# ross_comp.net
KiCad netlist of a schematic drawn in EAGLE
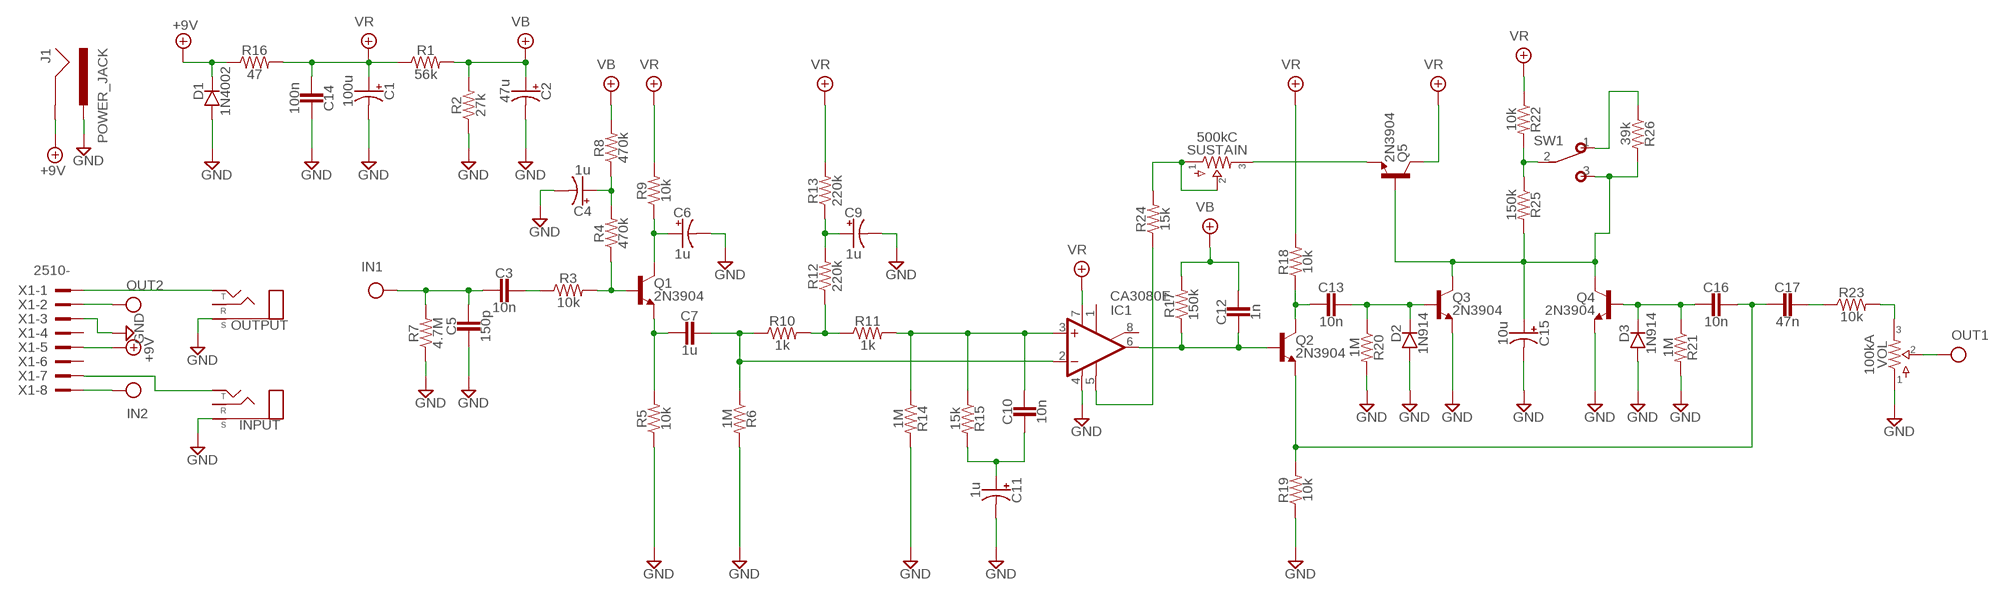
[diagram p0: schematic, sheet 1]

(export (version "E")
  (design (tool "Eeschema 10.0.6"))
  (components
    (comp (ref "C1")
      (value "100u")
      (footprint "eagle-import:040_020")
      (libsource (lib "eagle-import") (part "0400"))
    )
    (comp (ref "C2")
      (value "47u")
      (footprint "eagle-import:040_020")
      (libsource (lib "eagle-import") (part "0400"))
    )
    (comp (ref "C3")
      (value "10n")
      (footprint "eagle-import:BOX_SMALL")
      (libsource (lib "eagle-import") (part "CER/FILMBOX.1"))
    )
    (comp (ref "C4")
      (value "1u")
      (footprint "eagle-import:040_020")
      (libsource (lib "eagle-import") (part "0400"))
    )
    (comp (ref "C5")
      (value "150p")
      (footprint "eagle-import:050X030_025_2")
      (libsource (lib "eagle-import") (part "CER/FILM2"))
    )
    (comp (ref "C6")
      (value "1u")
      (footprint "eagle-import:040_020")
      (libsource (lib "eagle-import") (part "0400"))
    )
    (comp (ref "C7")
      (value "1u")
      (footprint "eagle-import:BOX_BIG")
      (libsource (lib "eagle-import") (part "CER/FILMBOX.3"))
    )
    (comp (ref "C9")
      (value "1u")
      (footprint "eagle-import:040_020")
      (libsource (lib "eagle-import") (part "0400"))
    )
    (comp (ref "C10")
      (value "10n")
      (footprint "eagle-import:BOX_SMALL")
      (libsource (lib "eagle-import") (part "CER/FILMBOX.1"))
    )
    (comp (ref "C11")
      (value "1u")
      (footprint "eagle-import:040_020")
      (libsource (lib "eagle-import") (part "0400"))
    )
    (comp (ref "C12")
      (value "1n")
      (footprint "eagle-import:BOX_SMALL")
      (libsource (lib "eagle-import") (part "CER/FILMBOX.1"))
    )
    (comp (ref "C13")
      (value "10n")
      (footprint "eagle-import:BOX_SMALL")
      (libsource (lib "eagle-import") (part "CER/FILMBOX.1"))
    )
    (comp (ref "C14")
      (value "100n")
      (footprint "eagle-import:BOX_SMALL")
      (libsource (lib "eagle-import") (part "CER/FILMBOX.1"))
    )
    (comp (ref "C15")
      (value "10u")
      (footprint "eagle-import:040_020")
      (libsource (lib "eagle-import") (part "0400"))
    )
    (comp (ref "C16")
      (value "10n")
      (footprint "eagle-import:BOX_SMALL")
      (libsource (lib "eagle-import") (part "CER/FILMBOX.1"))
    )
    (comp (ref "C17")
      (value "47n")
      (footprint "eagle-import:BOX_SMALL")
      (libsource (lib "eagle-import") (part "CER/FILMBOX.1"))
    )
    (comp (ref "D1")
      (value "1N4002")
      (footprint "eagle-import:DO41-2")
      (libsource (lib "eagle-import") (part "DO41.2"))
    )
    (comp (ref "D2")
      (value "1N914")
      (footprint "eagle-import:DO35-2")
      (libsource (lib "eagle-import") (part "DO35.2"))
    )
    (comp (ref "D3")
      (value "1N914")
      (footprint "eagle-import:DO35-2")
      (libsource (lib "eagle-import") (part "DO35.2"))
    )
    (comp (ref "IC1")
      (value "CA3080E")
      (footprint "eagle-import:DIL08")
      (libsource (lib "eagle-import") (part "3080TH"))
    )
    (comp (ref "INPUT")
      (value "STEREONMJ")
      (footprint "eagle-import:NMJ6HCD2")
      (libsource (lib "eagle-import") (part "STEREONMJ"))
    )
    (comp (ref "J1")
      (value "POWER_JACK")
      (footprint "eagle-import:POWER_JACK_PTH")
      (libsource (lib "eagle-import") (part "POWER_JACK"))
    )
    (comp (ref "OUTPUT")
      (value "STEREONMJ")
      (footprint "eagle-import:NMJ6HCD2")
      (libsource (lib "eagle-import") (part "STEREONMJ"))
    )
    (comp (ref "Q1")
      (value "2N3904")
      (footprint "eagle-import:TO92-")
      (libsource (lib "eagle-import") (part "2N3904"))
    )
    (comp (ref "Q2")
      (value "2N3904")
      (footprint "eagle-import:TO92-")
      (libsource (lib "eagle-import") (part "2N3904"))
    )
    (comp (ref "Q3")
      (value "2N3904")
      (footprint "eagle-import:TO92-")
      (libsource (lib "eagle-import") (part "2N3904"))
    )
    (comp (ref "Q4")
      (value "2N3904")
      (footprint "eagle-import:TO92-")
      (libsource (lib "eagle-import") (part "2N3904"))
    )
    (comp (ref "Q5")
      (value "2N3904")
      (footprint "eagle-import:TO92-")
      (libsource (lib "eagle-import") (part "2N3904"))
    )
    (comp (ref "R1")
      (value "56k")
      (footprint "eagle-import:R0207_3")
      (libsource (lib "eagle-import") (part "R_.3B"))
    )
    (comp (ref "R2")
      (value "27k")
      (footprint "eagle-import:R0207_3")
      (libsource (lib "eagle-import") (part "R_.3B"))
    )
    (comp (ref "R3")
      (value "10k")
      (footprint "eagle-import:R0207_3")
      (libsource (lib "eagle-import") (part "R_.3B"))
    )
    (comp (ref "R4")
      (value "470k")
      (footprint "eagle-import:R0207_3")
      (libsource (lib "eagle-import") (part "R_.3B"))
    )
    (comp (ref "R5")
      (value "10k")
      (footprint "eagle-import:R0207_3")
      (libsource (lib "eagle-import") (part "R_.3B"))
    )
    (comp (ref "R6")
      (value "1M")
      (footprint "eagle-import:R0207_3")
      (libsource (lib "eagle-import") (part "R_.3B"))
    )
    (comp (ref "R7")
      (value "4.7M")
      (footprint "eagle-import:R0207_3")
      (libsource (lib "eagle-import") (part "R_.3B"))
    )
    (comp (ref "R8")
      (value "470k")
      (footprint "eagle-import:R0207_3")
      (libsource (lib "eagle-import") (part "R_.3B"))
    )
    (comp (ref "R9")
      (value "10k")
      (footprint "eagle-import:R0207_3")
      (libsource (lib "eagle-import") (part "R_.3B"))
    )
    (comp (ref "R10")
      (value "1k")
      (footprint "eagle-import:R0207_3")
      (libsource (lib "eagle-import") (part "R_.3B"))
    )
    (comp (ref "R11")
      (value "1k")
      (footprint "eagle-import:R0207_3")
      (libsource (lib "eagle-import") (part "R_.3B"))
    )
    (comp (ref "R12")
      (value "220k")
      (footprint "eagle-import:R0207_3")
      (libsource (lib "eagle-import") (part "R_.3B"))
    )
    (comp (ref "R13")
      (value "220k")
      (footprint "eagle-import:R0207_3")
      (libsource (lib "eagle-import") (part "R_.3B"))
    )
    (comp (ref "R14")
      (value "1M")
      (footprint "eagle-import:R0207_3")
      (libsource (lib "eagle-import") (part "R_.3B"))
    )
    (comp (ref "R15")
      (value "15k")
      (footprint "eagle-import:R0207_3")
      (libsource (lib "eagle-import") (part "R_.3B"))
    )
    (comp (ref "R16")
      (value "47")
      (footprint "eagle-import:R0207_3")
      (libsource (lib "eagle-import") (part "R_.3B"))
    )
    (comp (ref "R17")
      (value "150k")
      (footprint "eagle-import:R0207_3")
      (libsource (lib "eagle-import") (part "R_.3B"))
    )
    (comp (ref "R18")
      (value "10k")
      (footprint "eagle-import:R0207_3")
      (libsource (lib "eagle-import") (part "R_.3B"))
    )
    (comp (ref "R19")
      (value "10k")
      (footprint "eagle-import:R0207_3")
      (libsource (lib "eagle-import") (part "R_.3B"))
    )
    (comp (ref "R20")
      (value "1M")
      (footprint "eagle-import:R0207_3")
      (libsource (lib "eagle-import") (part "R_.3B"))
    )
    (comp (ref "R21")
      (value "1M")
      (footprint "eagle-import:R0207_3")
      (libsource (lib "eagle-import") (part "R_.3B"))
    )
    (comp (ref "R22")
      (value "10k")
      (footprint "eagle-import:R0207_3")
      (libsource (lib "eagle-import") (part "R_.3B"))
    )
    (comp (ref "R23")
      (value "10k")
      (footprint "eagle-import:R0207_3")
      (libsource (lib "eagle-import") (part "R_.3B"))
    )
    (comp (ref "R24")
      (value "15k")
      (footprint "eagle-import:R0207_3")
      (libsource (lib "eagle-import") (part "R_.3B"))
    )
    (comp (ref "R25")
      (value "150k")
      (footprint "eagle-import:R0207_3")
      (libsource (lib "eagle-import") (part "R_.3B"))
    )
    (comp (ref "R26")
      (value "39k")
      (footprint "eagle-import:R0207_3")
      (libsource (lib "eagle-import") (part "R_.3B"))
    )
    (comp (ref "SUSTAIN")
      (value "500kC")
      (footprint "eagle-import:16MM")
      (libsource (lib "eagle-import") (part "POTS16MM"))
    )
    (comp (ref "SW1")
      (value "SPDT")
      (footprint "eagle-import:M9040P")
      (libsource (lib "eagle-import") (part "SPDT"))
    )
    (comp (ref "VOL")
      (value "100kA")
      (footprint "eagle-import:16MM")
      (libsource (lib "eagle-import") (part "POTS16MM"))
    )
    (comp (ref "X1")
      (value "2510-")
      (footprint "eagle-import:PAK100_2500-10")
      (fields (field (name "MF") "3M") (field (name "MPN") "2510-6002UB"))
      (libsource (lib "eagle-import") (part "2510-"))
    )
  )
  (nets
    (net (code "1") (name "+9V") (class "Default")
      (node (ref "D1") (pin "C") (pinfunction "C_C") (pintype "passive"))
      (node (ref "J1") (pin "GND") (pinfunction "GND_GND") (pintype "bidirectional"))
      (node (ref "R16") (pin "1") (pinfunction "1_1") (pintype "passive"))
      (node (ref "X1") (pin "5") (pinfunction "KL_5") (pintype "passive"))
    )
    (net (code "2") (name "GND") (class "Default")
      (node (ref "C1") (pin "-") (pinfunction "-_-") (pintype "passive"))
      (node (ref "C11") (pin "-") (pinfunction "-_-") (pintype "passive"))
      (node (ref "C14") (pin "1") (pinfunction "1_1") (pintype "passive"))
      (node (ref "C15") (pin "-") (pinfunction "-_-") (pintype "passive"))
      (node (ref "C2") (pin "-") (pinfunction "-_-") (pintype "passive"))
      (node (ref "C4") (pin "-") (pinfunction "-_-") (pintype "passive"))
      (node (ref "C5") (pin "2") (pinfunction "2_2") (pintype "passive"))
      (node (ref "C6") (pin "-") (pinfunction "-_-") (pintype "passive"))
      (node (ref "C9") (pin "-") (pinfunction "-_-") (pintype "passive"))
      (node (ref "D1") (pin "A") (pinfunction "A_A") (pintype "passive"))
      (node (ref "D2") (pin "A") (pinfunction "A_A") (pintype "passive"))
      (node (ref "D3") (pin "A") (pinfunction "A_A") (pintype "passive"))
      (node (ref "IC1") (pin "4") (pinfunction "V-_4") (pintype "power_in"))
      (node (ref "INPUT") (pin "S") (pinfunction "S_S") (pintype "passive"))
      (node (ref "J1") (pin "PWR") (pinfunction "PWR_PWR") (pintype "bidirectional"))
      (node (ref "OUTPUT") (pin "S") (pinfunction "S_S") (pintype "passive"))
      (node (ref "Q3") (pin "3") (pinfunction "E_3") (pintype "passive"))
      (node (ref "Q4") (pin "3") (pinfunction "E_3") (pintype "passive"))
      (node (ref "R14") (pin "2") (pinfunction "2_2") (pintype "passive"))
      (node (ref "R19") (pin "1") (pinfunction "1_1") (pintype "passive"))
      (node (ref "R2") (pin "1") (pinfunction "1_1") (pintype "passive"))
      (node (ref "R20") (pin "2") (pinfunction "2_2") (pintype "passive"))
      (node (ref "R21") (pin "2") (pinfunction "2_2") (pintype "passive"))
      (node (ref "R5") (pin "1") (pinfunction "1_1") (pintype "passive"))
      (node (ref "R6") (pin "2") (pinfunction "2_2") (pintype "passive"))
      (node (ref "R7") (pin "1") (pinfunction "1_1") (pintype "passive"))
      (node (ref "VOL") (pin "1") (pinfunction "1_1") (pintype "passive"))
      (node (ref "X1") (pin "3") (pinfunction "KL_3") (pintype "passive"))
    )
    (net (code "3") (name "IN") (class "Default")
      (node (ref "C3") (pin "2") (pinfunction "2_2") (pintype "passive"))
      (node (ref "C5") (pin "1") (pinfunction "1_1") (pintype "passive"))
      (node (ref "R7") (pin "2") (pinfunction "2_2") (pintype "passive"))
      (node (ref "X1") (pin "8") (pinfunction "KL_8") (pintype "passive"))
    )
    (net (code "4") (name "Net-(C3-Pad1)") (class "Default")
      (node (ref "C3") (pin "1") (pinfunction "1_1") (pintype "passive"))
      (node (ref "R3") (pin "1") (pinfunction "1_1") (pintype "passive"))
    )
    (net (code "5") (name "Net-(C4-Pad+)") (class "Default")
      (node (ref "C4") (pin "+") (pinfunction "+_+") (pintype "passive"))
      (node (ref "R4") (pin "2") (pinfunction "2_2") (pintype "passive"))
      (node (ref "R8") (pin "1") (pinfunction "1_1") (pintype "passive"))
    )
    (net (code "6") (name "Net-(C9-Pad+)") (class "Default")
      (node (ref "C9") (pin "+") (pinfunction "+_+") (pintype "passive"))
      (node (ref "R12") (pin "2") (pinfunction "2_2") (pintype "passive"))
      (node (ref "R13") (pin "1") (pinfunction "1_1") (pintype "passive"))
    )
    (net (code "7") (name "Net-(C10-Pad2)") (class "Default")
      (node (ref "C10") (pin "2") (pinfunction "2_2") (pintype "passive"))
      (node (ref "C11") (pin "+") (pinfunction "+_+") (pintype "passive"))
      (node (ref "R15") (pin "2") (pinfunction "2_2") (pintype "passive"))
    )
    (net (code "8") (name "Net-(C17-Pad1)") (class "Default")
      (node (ref "C17") (pin "1") (pinfunction "1_1") (pintype "passive"))
      (node (ref "R23") (pin "1") (pinfunction "1_1") (pintype "passive"))
    )
    (net (code "9") (name "Net-(IC1-+IN)") (class "Default")
      (node (ref "C10") (pin "1") (pinfunction "1_1") (pintype "passive"))
      (node (ref "IC1") (pin "3") (pinfunction "+IN_3") (pintype "input"))
      (node (ref "R11") (pin "2") (pinfunction "2_2") (pintype "passive"))
      (node (ref "R14") (pin "1") (pinfunction "1_1") (pintype "passive"))
      (node (ref "R15") (pin "1") (pinfunction "1_1") (pintype "passive"))
    )
    (net (code "10") (name "Net-(IC1--IN)") (class "Default")
      (node (ref "C7") (pin "1") (pinfunction "1_1") (pintype "passive"))
      (node (ref "IC1") (pin "2") (pinfunction "-IN_2") (pintype "input"))
      (node (ref "R10") (pin "1") (pinfunction "1_1") (pintype "passive"))
      (node (ref "R6") (pin "1") (pinfunction "1_1") (pintype "passive"))
    )
    (net (code "11") (name "Net-(IC1-OPT)") (class "Default")
      (node (ref "IC1") (pin "5") (pinfunction "OPT_5") (pintype "passive"))
      (node (ref "R24") (pin "1") (pinfunction "1_1") (pintype "passive"))
    )
    (net (code "12") (name "Net-(IC1-OUT)") (class "Default")
      (node (ref "C12") (pin "2") (pinfunction "2_2") (pintype "passive"))
      (node (ref "IC1") (pin "6") (pinfunction "OUT_6") (pintype "output"))
      (node (ref "Q2") (pin "2") (pinfunction "B_2") (pintype "passive"))
      (node (ref "R17") (pin "1") (pinfunction "1_1") (pintype "passive"))
    )
    (net (code "13") (name "Net-(Q1-B)") (class "Default")
      (node (ref "Q1") (pin "2") (pinfunction "B_2") (pintype "passive"))
      (node (ref "R3") (pin "2") (pinfunction "2_2") (pintype "passive"))
      (node (ref "R4") (pin "1") (pinfunction "1_1") (pintype "passive"))
    )
    (net (code "14") (name "Net-(Q1-C)") (class "Default")
      (node (ref "C6") (pin "+") (pinfunction "+_+") (pintype "passive"))
      (node (ref "Q1") (pin "1") (pinfunction "C_1") (pintype "passive"))
      (node (ref "R9") (pin "1") (pinfunction "1_1") (pintype "passive"))
    )
    (net (code "15") (name "Net-(Q1-E)") (class "Default")
      (node (ref "C7") (pin "2") (pinfunction "2_2") (pintype "passive"))
      (node (ref "Q1") (pin "3") (pinfunction "E_3") (pintype "passive"))
      (node (ref "R5") (pin "2") (pinfunction "2_2") (pintype "passive"))
    )
    (net (code "16") (name "Net-(Q2-C)") (class "Default")
      (node (ref "C13") (pin "2") (pinfunction "2_2") (pintype "passive"))
      (node (ref "Q2") (pin "1") (pinfunction "C_1") (pintype "passive"))
      (node (ref "R18") (pin "1") (pinfunction "1_1") (pintype "passive"))
    )
    (net (code "17") (name "Net-(Q2-E)") (class "Default")
      (node (ref "C16") (pin "1") (pinfunction "1_1") (pintype "passive"))
      (node (ref "C17") (pin "2") (pinfunction "2_2") (pintype "passive"))
      (node (ref "Q2") (pin "3") (pinfunction "E_3") (pintype "passive"))
      (node (ref "R19") (pin "2") (pinfunction "2_2") (pintype "passive"))
    )
    (net (code "18") (name "Net-(Q3-B)") (class "Default")
      (node (ref "C13") (pin "1") (pinfunction "1_1") (pintype "passive"))
      (node (ref "D2") (pin "C") (pinfunction "C_C") (pintype "passive"))
      (node (ref "Q3") (pin "2") (pinfunction "B_2") (pintype "passive"))
      (node (ref "R20") (pin "1") (pinfunction "1_1") (pintype "passive"))
    )
    (net (code "19") (name "Net-(Q3-C)") (class "Default")
      (node (ref "C15") (pin "+") (pinfunction "+_+") (pintype "passive"))
      (node (ref "Q3") (pin "1") (pinfunction "C_1") (pintype "passive"))
      (node (ref "Q4") (pin "1") (pinfunction "C_1") (pintype "passive"))
      (node (ref "Q5") (pin "2") (pinfunction "B_2") (pintype "passive"))
      (node (ref "R25") (pin "2") (pinfunction "2_2") (pintype "passive"))
      (node (ref "R26") (pin "2") (pinfunction "2_2") (pintype "passive"))
      (node (ref "SW1") (pin "3") (pinfunction "S_3") (pintype "passive"))
    )
    (net (code "20") (name "Net-(Q4-B)") (class "Default")
      (node (ref "C16") (pin "2") (pinfunction "2_2") (pintype "passive"))
      (node (ref "D3") (pin "C") (pinfunction "C_C") (pintype "passive"))
      (node (ref "Q4") (pin "2") (pinfunction "B_2") (pintype "passive"))
      (node (ref "R21") (pin "1") (pinfunction "1_1") (pintype "passive"))
    )
    (net (code "21") (name "Net-(Q5-E)") (class "Default")
      (node (ref "Q5") (pin "3") (pinfunction "E_3") (pintype "passive"))
      (node (ref "SUSTAIN") (pin "3") (pinfunction "3_3") (pintype "passive"))
    )
    (net (code "22") (name "Net-(R10-Pad2)") (class "Default")
      (node (ref "R10") (pin "2") (pinfunction "2_2") (pintype "passive"))
      (node (ref "R11") (pin "1") (pinfunction "1_1") (pintype "passive"))
      (node (ref "R12") (pin "1") (pinfunction "1_1") (pintype "passive"))
    )
    (net (code "23") (name "Net-(R23-Pad2)") (class "Default")
      (node (ref "R23") (pin "2") (pinfunction "2_2") (pintype "passive"))
      (node (ref "VOL") (pin "3") (pinfunction "3_3") (pintype "passive"))
    )
    (net (code "24") (name "Net-(R24-Pad2)") (class "Default")
      (node (ref "R24") (pin "2") (pinfunction "2_2") (pintype "passive"))
      (node (ref "SUSTAIN") (pin "1") (pinfunction "1_1") (pintype "passive"))
      (node (ref "SUSTAIN") (pin "2") (pinfunction "2_2") (pintype "passive"))
    )
    (net (code "25") (name "Net-(SW1-O)") (class "Default")
      (node (ref "R26") (pin "1") (pinfunction "1_1") (pintype "passive"))
      (node (ref "SW1") (pin "1") (pinfunction "O_1") (pintype "passive"))
    )
    (net (code "26") (name "Net-(SW1-P)") (class "Default")
      (node (ref "R22") (pin "2") (pinfunction "2_2") (pintype "passive"))
      (node (ref "R25") (pin "1") (pinfunction "1_1") (pintype "passive"))
      (node (ref "SW1") (pin "2") (pinfunction "P_2") (pintype "passive"))
    )
    (net (code "27") (name "Net-(X1A-KL)") (class "Default")
      (node (ref "OUTPUT") (pin "T") (pinfunction "T_T") (pintype "passive"))
      (node (ref "X1") (pin "1") (pinfunction "KL_1") (pintype "passive"))
    )
    (net (code "28") (name "Net-(X1G-KL)") (class "Default")
      (node (ref "INPUT") (pin "T") (pinfunction "T_T") (pintype "passive"))
      (node (ref "X1") (pin "7") (pinfunction "KL_7") (pintype "passive"))
    )
    (net (code "29") (name "OUT") (class "Default")
      (node (ref "VOL") (pin "2") (pinfunction "2_2") (pintype "passive"))
      (node (ref "X1") (pin "2") (pinfunction "KL_2") (pintype "passive"))
    )
    (net (code "30") (name "VB") (class "Default")
      (node (ref "C12") (pin "1") (pinfunction "1_1") (pintype "passive"))
      (node (ref "C2") (pin "+") (pinfunction "+_+") (pintype "passive"))
      (node (ref "R1") (pin "2") (pinfunction "2_2") (pintype "passive"))
      (node (ref "R17") (pin "2") (pinfunction "2_2") (pintype "passive"))
      (node (ref "R2") (pin "2") (pinfunction "2_2") (pintype "passive"))
      (node (ref "R8") (pin "2") (pinfunction "2_2") (pintype "passive"))
    )
    (net (code "31") (name "VR") (class "Default")
      (node (ref "C1") (pin "+") (pinfunction "+_+") (pintype "passive"))
      (node (ref "C14") (pin "2") (pinfunction "2_2") (pintype "passive"))
      (node (ref "IC1") (pin "7") (pinfunction "V+_7") (pintype "power_in"))
      (node (ref "Q5") (pin "1") (pinfunction "C_1") (pintype "passive"))
      (node (ref "R1") (pin "1") (pinfunction "1_1") (pintype "passive"))
      (node (ref "R13") (pin "2") (pinfunction "2_2") (pintype "passive"))
      (node (ref "R16") (pin "2") (pinfunction "2_2") (pintype "passive"))
      (node (ref "R18") (pin "2") (pinfunction "2_2") (pintype "passive"))
      (node (ref "R22") (pin "1") (pinfunction "1_1") (pintype "passive"))
      (node (ref "R9") (pin "2") (pinfunction "2_2") (pintype "passive"))
    )
    (net (code "32") (name "unconnected-(IC1-ON1-Pad1)") (class "Default")
      (node (ref "IC1") (pin "1") (pinfunction "ON1_1") (pintype "passive"))
    )
    (net (code "33") (name "unconnected-(IC1-ON2-Pad8)") (class "Default")
      (node (ref "IC1") (pin "8") (pinfunction "ON2_8") (pintype "passive"))
    )
    (net (code "34") (name "unconnected-(INPUT-PadR)") (class "Default")
      (node (ref "INPUT") (pin "R") (pinfunction "R_R") (pintype "passive"))
    )
    (net (code "35") (name "unconnected-(OUTPUT-PadR)") (class "Default")
      (node (ref "OUTPUT") (pin "R") (pinfunction "R_R") (pintype "passive"))
    )
    (net (code "36") (name "unconnected-(X1D-KL-Pad4)") (class "Default")
      (node (ref "X1") (pin "4") (pinfunction "KL_4") (pintype "passive"))
    )
    (net (code "37") (name "unconnected-(X1F-KL-Pad6)") (class "Default")
      (node (ref "X1") (pin "6") (pinfunction "KL_6") (pintype "passive"))
    )
  )
)
